# Keg_Cop_-_Main.net
KiCad netlist of a schematic drawn in EAGLE
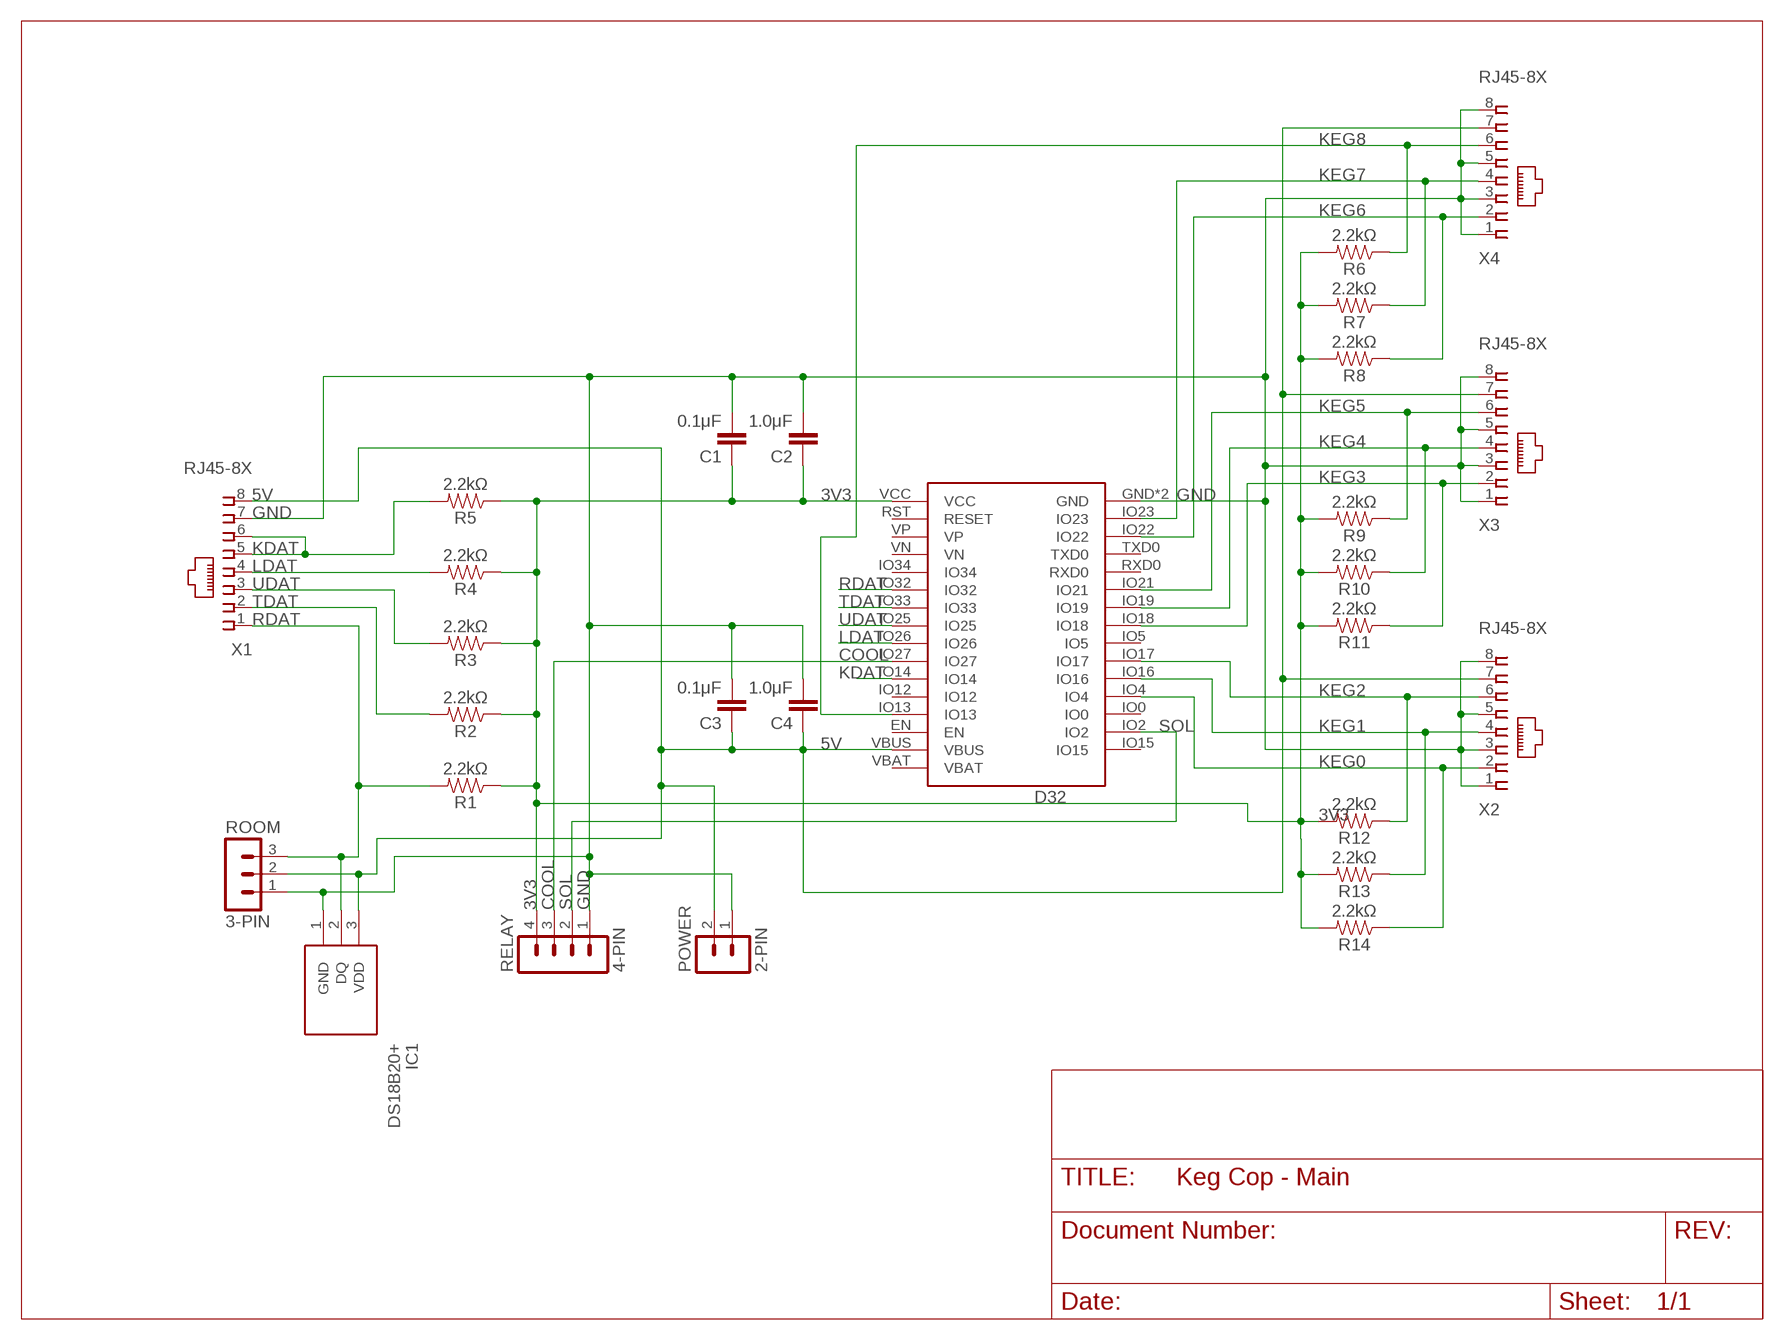
[diagram p0: schematic, sheet 1]

(export (version "E")
  (design (tool "Eeschema 10.0.6"))
  (components
    (comp (ref "C1")
      (value "0.1μF")
      (footprint "eagle-import:CAP_PTH-2.54")
      (libsource (lib "eagle-import") (part "CAP_CERAMIC_2.54"))
    )
    (comp (ref "C2")
      (value "1.0μF")
      (footprint "eagle-import:CAP_PTH-2.54")
      (libsource (lib "eagle-import") (part "CAP_CERAMIC_2.54"))
    )
    (comp (ref "C3")
      (value "0.1μF")
      (footprint "eagle-import:CAP_PTH-2.54")
      (libsource (lib "eagle-import") (part "CAP_CERAMIC_2.54"))
    )
    (comp (ref "C4")
      (value "1.0μF")
      (footprint "eagle-import:CAP_PTH-2.54")
      (libsource (lib "eagle-import") (part "CAP_CERAMIC_2.54"))
    )
    (comp (ref "D32")
      (value "Lolin D32")
      (footprint "eagle-import:D32_NO_BATT")
      (libsource (lib "eagle-import") (part "WEMOS-D32D32_NO_BATT"))
    )
    (comp (ref "IC1")
      (value "DS18B20+")
      (footprint "eagle-import:TO-92")
      (fields (field (name "MOUSER_PART_NUMBER") "700-DS18B20+"))
      (libsource (lib "eagle-import") (part "DS18B20+"))
    )
    (comp (ref "POWER")
      (value "2-PIN")
      (footprint "eagle-import:HDR-2_VERT")
      (libsource (lib "eagle-import") (part "HDR-2"))
    )
    (comp (ref "R1")
      (value "2.2kΩ")
      (footprint "eagle-import:AXIAL-0.3")
      (libsource (lib "eagle-import") (part "RESISTORAXIAL-0.3"))
    )
    (comp (ref "R2")
      (value "2.2kΩ")
      (footprint "eagle-import:AXIAL-0.3")
      (libsource (lib "eagle-import") (part "RESISTORAXIAL-0.3"))
    )
    (comp (ref "R3")
      (value "2.2kΩ")
      (footprint "eagle-import:AXIAL-0.3")
      (libsource (lib "eagle-import") (part "RESISTORAXIAL-0.3"))
    )
    (comp (ref "R4")
      (value "2.2kΩ")
      (footprint "eagle-import:AXIAL-0.3")
      (libsource (lib "eagle-import") (part "RESISTORAXIAL-0.3"))
    )
    (comp (ref "R5")
      (value "2.2kΩ")
      (footprint "eagle-import:AXIAL-0.3")
      (libsource (lib "eagle-import") (part "RESISTORAXIAL-0.3"))
    )
    (comp (ref "R6")
      (value "2.2kΩ")
      (footprint "eagle-import:AXIAL-0.3")
      (libsource (lib "eagle-import") (part "RESISTORAXIAL-0.3"))
    )
    (comp (ref "R7")
      (value "2.2kΩ")
      (footprint "eagle-import:AXIAL-0.3")
      (libsource (lib "eagle-import") (part "RESISTORAXIAL-0.3"))
    )
    (comp (ref "R8")
      (value "2.2kΩ")
      (footprint "eagle-import:AXIAL-0.3")
      (libsource (lib "eagle-import") (part "RESISTORAXIAL-0.3"))
    )
    (comp (ref "R9")
      (value "2.2kΩ")
      (footprint "eagle-import:AXIAL-0.3")
      (libsource (lib "eagle-import") (part "RESISTORAXIAL-0.3"))
    )
    (comp (ref "R10")
      (value "2.2kΩ")
      (footprint "eagle-import:AXIAL-0.3")
      (libsource (lib "eagle-import") (part "RESISTORAXIAL-0.3"))
    )
    (comp (ref "R11")
      (value "2.2kΩ")
      (footprint "eagle-import:AXIAL-0.3")
      (libsource (lib "eagle-import") (part "RESISTORAXIAL-0.3"))
    )
    (comp (ref "R12")
      (value "2.2kΩ")
      (footprint "eagle-import:AXIAL-0.3")
      (libsource (lib "eagle-import") (part "RESISTORAXIAL-0.3"))
    )
    (comp (ref "R13")
      (value "2.2kΩ")
      (footprint "eagle-import:AXIAL-0.3")
      (libsource (lib "eagle-import") (part "RESISTORAXIAL-0.3"))
    )
    (comp (ref "R14")
      (value "2.2kΩ")
      (footprint "eagle-import:AXIAL-0.3")
      (libsource (lib "eagle-import") (part "RESISTORAXIAL-0.3"))
    )
    (comp (ref "RELAY")
      (value "4-PIN")
      (footprint "eagle-import:MA04-1")
      (libsource (lib "eagle-import") (part "MA04-1"))
    )
    (comp (ref "ROOM")
      (value "3-PIN")
      (footprint "eagle-import:HDR-3_VERT")
      (libsource (lib "eagle-import") (part "HDR-3"))
    )
    (comp (ref "X1")
      (value "RJ45-8X")
      (footprint "eagle-import:RJ45-NO-SHIELD")
      (libsource (lib "eagle-import") (part "RJ45-8X"))
    )
    (comp (ref "X2")
      (value "RJ45-8X")
      (footprint "eagle-import:RJ45-NO-SHIELD")
      (libsource (lib "eagle-import") (part "RJ45-8X"))
    )
    (comp (ref "X3")
      (value "RJ45-8X")
      (footprint "eagle-import:RJ45-NO-SHIELD")
      (libsource (lib "eagle-import") (part "RJ45-8X"))
    )
    (comp (ref "X4")
      (value "RJ45-8X")
      (footprint "eagle-import:RJ45-NO-SHIELD")
      (libsource (lib "eagle-import") (part "RJ45-8X"))
    )
  )
  (nets
    (net (code "1") (name "/3V3") (class "Default")
      (node (ref "C1") (pin "1") (pinfunction "1_1") (pintype "passive"))
      (node (ref "C2") (pin "1") (pinfunction "1_1") (pintype "passive"))
      (node (ref "D32") (pin "VCC") (pinfunction "VCC_VCC") (pintype "power_in"))
      (node (ref "R1") (pin "P$1") (pinfunction "1_P$1") (pintype "passive"))
      (node (ref "R10") (pin "P$2") (pinfunction "2_P$2") (pintype "passive"))
      (node (ref "R11") (pin "P$2") (pinfunction "2_P$2") (pintype "passive"))
      (node (ref "R12") (pin "P$2") (pinfunction "2_P$2") (pintype "passive"))
      (node (ref "R13") (pin "P$2") (pinfunction "2_P$2") (pintype "passive"))
      (node (ref "R14") (pin "P$2") (pinfunction "2_P$2") (pintype "passive"))
      (node (ref "R2") (pin "P$1") (pinfunction "1_P$1") (pintype "passive"))
      (node (ref "R3") (pin "P$1") (pinfunction "1_P$1") (pintype "passive"))
      (node (ref "R4") (pin "P$1") (pinfunction "1_P$1") (pintype "passive"))
      (node (ref "R5") (pin "P$1") (pinfunction "1_P$1") (pintype "passive"))
      (node (ref "R6") (pin "P$2") (pinfunction "2_P$2") (pintype "passive"))
      (node (ref "R7") (pin "P$2") (pinfunction "2_P$2") (pintype "passive"))
      (node (ref "R8") (pin "P$2") (pinfunction "2_P$2") (pintype "passive"))
      (node (ref "R9") (pin "P$2") (pinfunction "2_P$2") (pintype "passive"))
      (node (ref "RELAY") (pin "4") (pinfunction "4_4") (pintype "passive"))
    )
    (net (code "2") (name "/5V") (class "Default")
      (node (ref "C3") (pin "1") (pinfunction "1_1") (pintype "passive"))
      (node (ref "C4") (pin "1") (pinfunction "1_1") (pintype "passive"))
      (node (ref "D32") (pin "VBUS") (pinfunction "VBUS_VBUS") (pintype "bidirectional"))
      (node (ref "IC1") (pin "3") (pinfunction "VDD_3") (pintype "power_in"))
      (node (ref "POWER") (pin "2") (pinfunction "2_2") (pintype "passive"))
      (node (ref "ROOM") (pin "2") (pinfunction "2_2") (pintype "passive"))
      (node (ref "X1") (pin "8") (pinfunction "8_8") (pintype "passive"))
      (node (ref "X2") (pin "7") (pinfunction "7_7") (pintype "passive"))
      (node (ref "X3") (pin "7") (pinfunction "7_7") (pintype "passive"))
      (node (ref "X4") (pin "7") (pinfunction "7_7") (pintype "passive"))
    )
    (net (code "3") (name "/COOL") (class "Default")
      (node (ref "D32") (pin "IO27") (pinfunction "IO27_IO27") (pintype "bidirectional"))
      (node (ref "RELAY") (pin "3") (pinfunction "3_3") (pintype "passive"))
    )
    (net (code "4") (name "/GND") (class "Default")
      (node (ref "C1") (pin "2") (pinfunction "2_2") (pintype "passive"))
      (node (ref "C2") (pin "2") (pinfunction "2_2") (pintype "passive"))
      (node (ref "C3") (pin "2") (pinfunction "2_2") (pintype "passive"))
      (node (ref "C4") (pin "2") (pinfunction "2_2") (pintype "passive"))
      (node (ref "D32") (pin "GND") (pinfunction "GND_GND") (pintype "power_in"))
      (node (ref "D32") (pin "GND2") (pinfunction "GND_GND2") (pintype "power_in"))
      (node (ref "IC1") (pin "1") (pinfunction "GND_1") (pintype "power_in"))
      (node (ref "POWER") (pin "1") (pinfunction "1_1") (pintype "passive"))
      (node (ref "RELAY") (pin "1") (pinfunction "1_1") (pintype "passive"))
      (node (ref "ROOM") (pin "1") (pinfunction "1_1") (pintype "passive"))
      (node (ref "X1") (pin "7") (pinfunction "7_7") (pintype "passive"))
      (node (ref "X2") (pin "1") (pinfunction "1_1") (pintype "passive"))
      (node (ref "X2") (pin "3") (pinfunction "3_3") (pintype "passive"))
      (node (ref "X2") (pin "5") (pinfunction "5_5") (pintype "passive"))
      (node (ref "X2") (pin "8") (pinfunction "8_8") (pintype "passive"))
      (node (ref "X3") (pin "1") (pinfunction "1_1") (pintype "passive"))
      (node (ref "X3") (pin "3") (pinfunction "3_3") (pintype "passive"))
      (node (ref "X3") (pin "5") (pinfunction "5_5") (pintype "passive"))
      (node (ref "X3") (pin "8") (pinfunction "8_8") (pintype "passive"))
      (node (ref "X4") (pin "1") (pinfunction "1_1") (pintype "passive"))
      (node (ref "X4") (pin "3") (pinfunction "3_3") (pintype "passive"))
      (node (ref "X4") (pin "5") (pinfunction "5_5") (pintype "passive"))
      (node (ref "X4") (pin "8") (pinfunction "8_8") (pintype "passive"))
    )
    (net (code "5") (name "/KDAT") (class "Default")
      (node (ref "D32") (pin "IO14") (pinfunction "IO14_IO14") (pintype "bidirectional"))
      (node (ref "R5") (pin "P$2") (pinfunction "2_P$2") (pintype "passive"))
      (node (ref "X1") (pin "5") (pinfunction "5_5") (pintype "passive"))
      (node (ref "X1") (pin "6") (pinfunction "6_6") (pintype "passive"))
    )
    (net (code "6") (name "/KEG0") (class "Default")
      (node (ref "D32") (pin "IO4") (pinfunction "IO4_IO4") (pintype "bidirectional"))
      (node (ref "R14") (pin "P$1") (pinfunction "1_P$1") (pintype "passive"))
      (node (ref "X2") (pin "2") (pinfunction "2_2") (pintype "passive"))
    )
    (net (code "7") (name "/KEG1") (class "Default")
      (node (ref "D32") (pin "IO16") (pinfunction "IO16_IO16") (pintype "bidirectional"))
      (node (ref "R13") (pin "P$1") (pinfunction "1_P$1") (pintype "passive"))
      (node (ref "X2") (pin "4") (pinfunction "4_4") (pintype "passive"))
    )
    (net (code "8") (name "/KEG2") (class "Default")
      (node (ref "D32") (pin "IO17") (pinfunction "IO17_IO17") (pintype "bidirectional"))
      (node (ref "R12") (pin "P$1") (pinfunction "1_P$1") (pintype "passive"))
      (node (ref "X2") (pin "6") (pinfunction "6_6") (pintype "passive"))
    )
    (net (code "9") (name "/KEG3") (class "Default")
      (node (ref "D32") (pin "IO18") (pinfunction "IO18_IO18") (pintype "bidirectional"))
      (node (ref "R11") (pin "P$1") (pinfunction "1_P$1") (pintype "passive"))
      (node (ref "X3") (pin "2") (pinfunction "2_2") (pintype "passive"))
    )
    (net (code "10") (name "/KEG4") (class "Default")
      (node (ref "D32") (pin "IO19") (pinfunction "IO19_IO19") (pintype "bidirectional"))
      (node (ref "R10") (pin "P$1") (pinfunction "1_P$1") (pintype "passive"))
      (node (ref "X3") (pin "4") (pinfunction "4_4") (pintype "passive"))
    )
    (net (code "11") (name "/KEG5") (class "Default")
      (node (ref "D32") (pin "IO21") (pinfunction "IO21_IO21") (pintype "bidirectional"))
      (node (ref "R9") (pin "P$1") (pinfunction "1_P$1") (pintype "passive"))
      (node (ref "X3") (pin "6") (pinfunction "6_6") (pintype "passive"))
    )
    (net (code "12") (name "/KEG6") (class "Default")
      (node (ref "D32") (pin "IO22") (pinfunction "IO22_IO22") (pintype "bidirectional"))
      (node (ref "R8") (pin "P$1") (pinfunction "1_P$1") (pintype "passive"))
      (node (ref "X4") (pin "2") (pinfunction "2_2") (pintype "passive"))
    )
    (net (code "13") (name "/KEG7") (class "Default")
      (node (ref "D32") (pin "IO23") (pinfunction "IO23_IO23") (pintype "bidirectional"))
      (node (ref "R7") (pin "P$1") (pinfunction "1_P$1") (pintype "passive"))
      (node (ref "X4") (pin "4") (pinfunction "4_4") (pintype "passive"))
    )
    (net (code "14") (name "/KEG8") (class "Default")
      (node (ref "D32") (pin "IO13") (pinfunction "IO13_IO13") (pintype "bidirectional"))
      (node (ref "R6") (pin "P$1") (pinfunction "1_P$1") (pintype "passive"))
      (node (ref "X4") (pin "6") (pinfunction "6_6") (pintype "passive"))
    )
    (net (code "15") (name "/LDAT") (class "Default")
      (node (ref "D32") (pin "IO26") (pinfunction "IO26_IO26") (pintype "bidirectional"))
      (node (ref "R4") (pin "P$2") (pinfunction "2_P$2") (pintype "passive"))
      (node (ref "X1") (pin "4") (pinfunction "4_4") (pintype "passive"))
    )
    (net (code "16") (name "/RDAT") (class "Default")
      (node (ref "D32") (pin "IO32") (pinfunction "IO32_IO32") (pintype "bidirectional"))
      (node (ref "IC1") (pin "2") (pinfunction "DQ_2") (pintype "bidirectional"))
      (node (ref "R1") (pin "P$2") (pinfunction "2_P$2") (pintype "passive"))
      (node (ref "ROOM") (pin "3") (pinfunction "3_3") (pintype "passive"))
      (node (ref "X1") (pin "1") (pinfunction "1_1") (pintype "passive"))
    )
    (net (code "17") (name "/SOL") (class "Default")
      (node (ref "D32") (pin "IO2") (pinfunction "IO2_IO2") (pintype "bidirectional"))
      (node (ref "RELAY") (pin "2") (pinfunction "2_2") (pintype "passive"))
    )
    (net (code "18") (name "/TDAT") (class "Default")
      (node (ref "D32") (pin "IO33") (pinfunction "IO33_IO33") (pintype "bidirectional"))
      (node (ref "R2") (pin "P$2") (pinfunction "2_P$2") (pintype "passive"))
      (node (ref "X1") (pin "2") (pinfunction "2_2") (pintype "passive"))
    )
    (net (code "19") (name "/UDAT") (class "Default")
      (node (ref "D32") (pin "IO25") (pinfunction "IO25_IO25") (pintype "bidirectional"))
      (node (ref "R3") (pin "P$2") (pinfunction "2_P$2") (pintype "passive"))
      (node (ref "X1") (pin "3") (pinfunction "3_3") (pintype "passive"))
    )
    (net (code "20") (name "unconnected-(D32-PadEN)") (class "Default")
      (node (ref "D32") (pin "EN") (pinfunction "EN_EN") (pintype "bidirectional"))
    )
    (net (code "21") (name "unconnected-(D32-PadIO0)") (class "Default")
      (node (ref "D32") (pin "IO0") (pinfunction "IO0_IO0") (pintype "bidirectional"))
    )
    (net (code "22") (name "unconnected-(D32-PadIO5)") (class "Default")
      (node (ref "D32") (pin "IO5") (pinfunction "IO5_IO5") (pintype "bidirectional"))
    )
    (net (code "23") (name "unconnected-(D32-PadIO12)") (class "Default")
      (node (ref "D32") (pin "IO12") (pinfunction "IO12_IO12") (pintype "bidirectional"))
    )
    (net (code "24") (name "unconnected-(D32-PadIO15)") (class "Default")
      (node (ref "D32") (pin "IO15") (pinfunction "IO15_IO15") (pintype "bidirectional"))
    )
    (net (code "25") (name "unconnected-(D32-PadIO34)") (class "Default")
      (node (ref "D32") (pin "IO34") (pinfunction "IO34_IO34") (pintype "bidirectional"))
    )
    (net (code "26") (name "unconnected-(D32-PadRXD0)") (class "Default")
      (node (ref "D32") (pin "RXD0") (pinfunction "RXD0_RXD0") (pintype "input"))
    )
    (net (code "27") (name "unconnected-(D32-PadTXD0)") (class "Default")
      (node (ref "D32") (pin "TXD0") (pinfunction "TXD0_TXD0") (pintype "output"))
    )
    (net (code "28") (name "unconnected-(D32-PadVBAT)") (class "Default")
      (node (ref "D32") (pin "VBAT") (pinfunction "VBAT_VBAT") (pintype "bidirectional"))
    )
    (net (code "29") (name "unconnected-(D32-PadVN)") (class "Default")
      (node (ref "D32") (pin "VN") (pinfunction "VN_VN") (pintype "bidirectional"))
    )
    (net (code "30") (name "unconnected-(D32-PadVP)") (class "Default")
      (node (ref "D32") (pin "VP") (pinfunction "VP_VP") (pintype "bidirectional"))
    )
    (net (code "31") (name "unconnected-(D32-RESET-PadRST)") (class "Default")
      (node (ref "D32") (pin "RST") (pinfunction "RESET_RST") (pintype "bidirectional"))
    )
  )
)
